# ecgschematic.net
KiCad netlist of a schematic drawn in Altium Designer
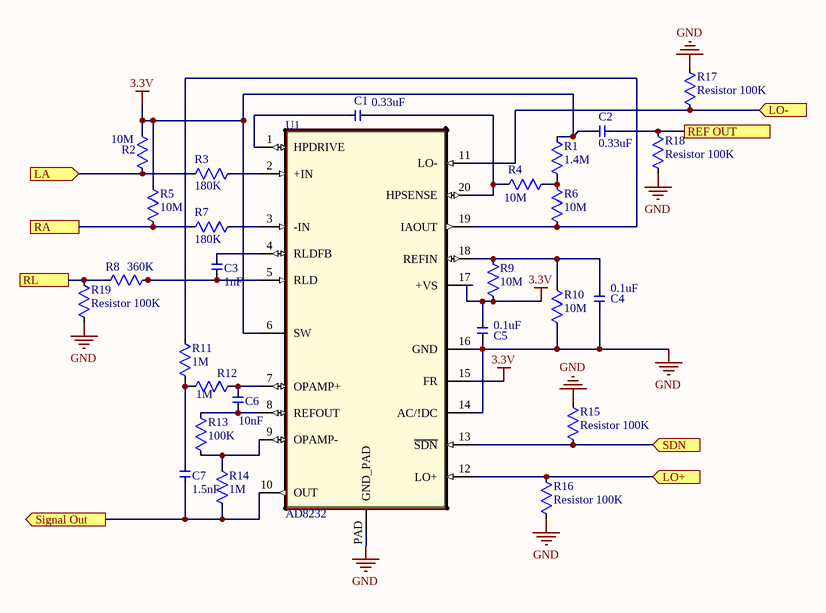
[diagram p0: ecgschematic.SchDoc]

(export (version "E")
  (design (tool "Eeschema 10.0.6"))
  (components
    (comp (ref "C1")
      (value "0.33uF")
      (footprint "Cap 0.330uF")
      (libsource (lib "Schlib1") (part "Cap 0.33uF"))
    )
    (comp (ref "C2")
      (value "0.33uF")
      (footprint "Cap 0.330uF")
      (libsource (lib "Schlib1") (part "Cap 0.33uF"))
    )
    (comp (ref "C3") (value "1nF") (footprint "CAP 1nF") (libsource (lib "Schlib1") (part "Cap 1nF")))
    (comp (ref "C4") (value "0.1uF") (footprint "CAP 0.1uF") (libsource (lib "Schlib1") (part "Cap 0.1uF")))
    (comp (ref "C5") (value "0.1uF") (footprint "CAP 0.1uF") (libsource (lib "Schlib1") (part "Cap 0.1uF")))
    (comp (ref "C6") (value "10nF") (footprint "CAP 10nF") (libsource (lib "Schlib1") (part "Cap 10nF")))
    (comp (ref "C7") (value "1.5nF") (footprint "CAP 1.5nF") (libsource (lib "Schlib1") (part "Cap 1.5nF")))
    (comp (ref "R1")
      (value "1.4M")
      (footprint "RESISTOR 1.4M")
      (libsource (lib "Schlib1") (part "Resistor 1.4M"))
    )
    (comp (ref "R2")
      (value "10M")
      (footprint "RESISTOR 10M")
      (libsource (lib "Schlib1") (part "Resistor 10M"))
    )
    (comp (ref "R3")
      (value "180K")
      (footprint "RESISTOR 180K")
      (libsource (lib "Schlib1") (part "Resistor 180K"))
    )
    (comp (ref "R4")
      (value "10M")
      (footprint "RESISTOR 10M")
      (libsource (lib "Schlib1") (part "Resistor 10M"))
    )
    (comp (ref "R5")
      (value "10M")
      (footprint "RESISTOR 10M")
      (libsource (lib "Schlib1") (part "Resistor 10M"))
    )
    (comp (ref "R6")
      (value "10M")
      (footprint "RESISTOR 10M")
      (libsource (lib "Schlib1") (part "Resistor 10M"))
    )
    (comp (ref "R7")
      (value "180K")
      (footprint "RESISTOR 180K")
      (libsource (lib "Schlib1") (part "Resistor 180K"))
    )
    (comp (ref "R8")
      (value "360K")
      (footprint "RESISTOR 360K")
      (libsource (lib "Schlib1") (part "Resistor 360K"))
    )
    (comp (ref "R9")
      (value "10M")
      (footprint "RESISTOR 10M")
      (libsource (lib "Schlib1") (part "Resistor 10M"))
    )
    (comp (ref "R10")
      (value "10M")
      (footprint "RESISTOR 10M")
      (libsource (lib "Schlib1") (part "Resistor 10M"))
    )
    (comp (ref "R11") (value "1M") (footprint "RESISTOR 1M") (libsource (lib "Schlib1") (part "Resistor 1M")))
    (comp (ref "R12") (value "1M") (footprint "RESISTOR 1M") (libsource (lib "Schlib1") (part "Resistor 1M")))
    (comp (ref "R13")
      (value "100K")
      (footprint "RESISTOR 100K")
      (libsource (lib "Schlib1") (part "Resistor 100K"))
    )
    (comp (ref "R14") (value "1M") (footprint "RESISTOR 1M") (libsource (lib "Schlib1") (part "Resistor 1M")))
    (comp (ref "R15")
      (value "Resistor 100K")
      (footprint "RESISTOR 100K")
      (libsource (lib "ECGHeartLib") (part "Resistor 100K"))
    )
    (comp (ref "R16")
      (value "Resistor 100K")
      (footprint "RESISTOR 100K")
      (libsource (lib "ECGHeartLib") (part "Resistor 100K"))
    )
    (comp (ref "R17")
      (value "Resistor 100K")
      (footprint "RESISTOR 100K")
      (libsource (lib "ECGHeartLib") (part "Resistor 100K"))
    )
    (comp (ref "R18")
      (value "Resistor 100K")
      (footprint "RESISTOR 100K")
      (libsource (lib "ECGHeartLib") (part "Resistor 100K"))
    )
    (comp (ref "R19")
      (value "Resistor 100K")
      (footprint "RESISTOR 100K")
      (libsource (lib "ECGHeartLib") (part "Resistor 100K"))
    )
    (comp (ref "U1")
      (value "AD8232")
      (footprint "*LFCSP_20_AD8232(Primary)")
      (description "ECG Front End 20-LFCSP-WQ _4x4_")
      (fields (field (name "MF") "Analog Devices"))
      (libsource (lib "AD8232") (part "AD8232"))
    )
  )
  (nets
    (net (code "1") (name "/LA") (class "Default")
      (node (ref "R2") (pin "1") (pinfunction "1_1") (pintype "passive"))
      (node (ref "R3") (pin "1") (pinfunction "1_1") (pintype "passive"))
    )
    (net (code "2") (name "/LO+") (class "Default")
      (node (ref "R16") (pin "2") (pinfunction "2_2") (pintype "passive"))
      (node (ref "U1") (pin "12") (pinfunction "LO+_12") (pintype "input"))
    )
    (net (code "3") (name "/LO-") (class "Default")
      (node (ref "R17") (pin "1") (pinfunction "1_1") (pintype "passive"))
      (node (ref "U1") (pin "11") (pinfunction "LO-_11") (pintype "input"))
    )
    (net (code "4") (name "/RA") (class "Default")
      (node (ref "R5") (pin "1") (pinfunction "1_1") (pintype "passive"))
      (node (ref "R7") (pin "1") (pinfunction "1_1") (pintype "passive"))
    )
    (net (code "5") (name "/REF OUT") (class "Default")
      (node (ref "C2") (pin "1") (pinfunction "4_1") (pintype "passive"))
      (node (ref "R18") (pin "2") (pinfunction "2_2") (pintype "passive"))
    )
    (net (code "6") (name "/RL") (class "Default")
      (node (ref "R19") (pin "2") (pinfunction "2_2") (pintype "passive"))
      (node (ref "R8") (pin "2") (pinfunction "2_2") (pintype "passive"))
    )
    (net (code "7") (name "/SDN") (class "Default")
      (node (ref "R15") (pin "1") (pinfunction "1_1") (pintype "passive"))
      (node (ref "U1") (pin "13") (pinfunction "~{SDN}_13") (pintype "input"))
    )
    (net (code "8") (name "/Signal Out") (class "Default")
      (node (ref "C7") (pin "2") (pinfunction "5_2") (pintype "passive"))
      (node (ref "R14") (pin "1") (pinfunction "1_1") (pintype "passive"))
      (node (ref "U1") (pin "10") (pinfunction "OUT_10") (pintype "output"))
    )
    (net (code "9") (name "3.3V") (class "Default")
      (node (ref "C2") (pin "2") (pinfunction "5_2") (pintype "passive"))
      (node (ref "C5") (pin "1") (pinfunction "4_1") (pintype "passive"))
      (node (ref "R1") (pin "2") (pinfunction "2_2") (pintype "passive"))
      (node (ref "R2") (pin "2") (pinfunction "2_2") (pintype "passive"))
      (node (ref "R5") (pin "2") (pinfunction "2_2") (pintype "passive"))
      (node (ref "R9") (pin "1") (pinfunction "1_1") (pintype "passive"))
      (node (ref "U1") (pin "15") (pinfunction "FR_15") (pintype "power_in"))
      (node (ref "U1") (pin "17") (pinfunction "+VS_17") (pintype "power_in"))
      (node (ref "U1") (pin "6") (pinfunction "SW_6") (pintype "power_in"))
    )
    (net (code "10") (name "GND") (class "Default")
      (node (ref "C4") (pin "2") (pinfunction "5_2") (pintype "passive"))
      (node (ref "C5") (pin "2") (pinfunction "5_2") (pintype "passive"))
      (node (ref "R10") (pin "1") (pinfunction "1_1") (pintype "passive"))
      (node (ref "R15") (pin "2") (pinfunction "2_2") (pintype "passive"))
      (node (ref "R16") (pin "1") (pinfunction "1_1") (pintype "passive"))
      (node (ref "R17") (pin "2") (pinfunction "2_2") (pintype "passive"))
      (node (ref "R18") (pin "1") (pinfunction "1_1") (pintype "passive"))
      (node (ref "R19") (pin "1") (pinfunction "1_1") (pintype "passive"))
      (node (ref "U1") (pin "14") (pinfunction "AC/!DC_14") (pintype "power_in"))
      (node (ref "U1") (pin "16") (pinfunction "GND_16") (pintype "power_in"))
      (node (ref "U1") (pin "PAD") (pinfunction "GND_PAD_PAD") (pintype "power_in"))
    )
    (net (code "11") (name "Net-(C1-4)") (class "Default")
      (node (ref "C1") (pin "1") (pinfunction "4_1") (pintype "passive"))
      (node (ref "R4") (pin "1") (pinfunction "1_1") (pintype "passive"))
      (node (ref "U1") (pin "20") (pinfunction "HPSENSE_20") (pintype "bidirectional"))
    )
    (net (code "12") (name "Net-(C1-5)") (class "Default")
      (node (ref "C1") (pin "2") (pinfunction "5_2") (pintype "passive"))
      (node (ref "U1") (pin "1") (pinfunction "HPDRIVE_1") (pintype "bidirectional"))
    )
    (net (code "13") (name "Net-(C3-4)") (class "Default")
      (node (ref "C3") (pin "1") (pinfunction "4_1") (pintype "passive"))
      (node (ref "U1") (pin "4") (pinfunction "RLDFB_4") (pintype "bidirectional"))
    )
    (net (code "14") (name "Net-(C3-5)") (class "Default")
      (node (ref "C3") (pin "2") (pinfunction "5_2") (pintype "passive"))
      (node (ref "R8") (pin "1") (pinfunction "1_1") (pintype "passive"))
      (node (ref "U1") (pin "5") (pinfunction "RLD_5") (pintype "input"))
    )
    (net (code "15") (name "Net-(C4-4)") (class "Default")
      (node (ref "C4") (pin "1") (pinfunction "4_1") (pintype "passive"))
      (node (ref "R10") (pin "2") (pinfunction "2_2") (pintype "passive"))
      (node (ref "R9") (pin "2") (pinfunction "2_2") (pintype "passive"))
      (node (ref "U1") (pin "18") (pinfunction "REFIN_18") (pintype "bidirectional"))
    )
    (net (code "16") (name "Net-(C6-4)") (class "Default")
      (node (ref "C6") (pin "1") (pinfunction "4_1") (pintype "passive"))
      (node (ref "R13") (pin "2") (pinfunction "2_2") (pintype "passive"))
      (node (ref "U1") (pin "8") (pinfunction "REFOUT_8") (pintype "bidirectional"))
    )
    (net (code "17") (name "Net-(C6-5)") (class "Default")
      (node (ref "C6") (pin "2") (pinfunction "5_2") (pintype "passive"))
      (node (ref "R12") (pin "2") (pinfunction "2_2") (pintype "passive"))
      (node (ref "U1") (pin "7") (pinfunction "OPAMP+_7") (pintype "bidirectional"))
    )
    (net (code "18") (name "Net-(C7-4)") (class "Default")
      (node (ref "C7") (pin "1") (pinfunction "4_1") (pintype "passive"))
      (node (ref "R11") (pin "1") (pinfunction "1_1") (pintype "passive"))
      (node (ref "R12") (pin "1") (pinfunction "1_1") (pintype "passive"))
    )
    (net (code "19") (name "Net-(R1-Pad1)") (class "Default")
      (node (ref "R1") (pin "1") (pinfunction "1_1") (pintype "passive"))
      (node (ref "R4") (pin "2") (pinfunction "2_2") (pintype "passive"))
      (node (ref "R6") (pin "2") (pinfunction "2_2") (pintype "passive"))
    )
    (net (code "20") (name "Net-(U1-+IN)") (class "Default")
      (node (ref "R3") (pin "2") (pinfunction "2_2") (pintype "passive"))
      (node (ref "U1") (pin "2") (pinfunction "+IN_2") (pintype "input"))
    )
    (net (code "21") (name "Net-(U1--IN)") (class "Default")
      (node (ref "R7") (pin "2") (pinfunction "2_2") (pintype "passive"))
      (node (ref "U1") (pin "3") (pinfunction "-IN_3") (pintype "input"))
    )
    (net (code "22") (name "Net-(U1-IAOUT)") (class "Default")
      (node (ref "R11") (pin "2") (pinfunction "2_2") (pintype "passive"))
      (node (ref "R6") (pin "1") (pinfunction "1_1") (pintype "passive"))
      (node (ref "U1") (pin "19") (pinfunction "IAOUT_19") (pintype "output"))
    )
    (net (code "23") (name "Net-(U1-OPAMP-)") (class "Default")
      (node (ref "R13") (pin "1") (pinfunction "1_1") (pintype "passive"))
      (node (ref "R14") (pin "2") (pinfunction "2_2") (pintype "passive"))
      (node (ref "U1") (pin "9") (pinfunction "OPAMP-_9") (pintype "bidirectional"))
    )
  )
)
